# SmallBatSAO.net
KiCad netlist of a schematic drawn in EAGLE
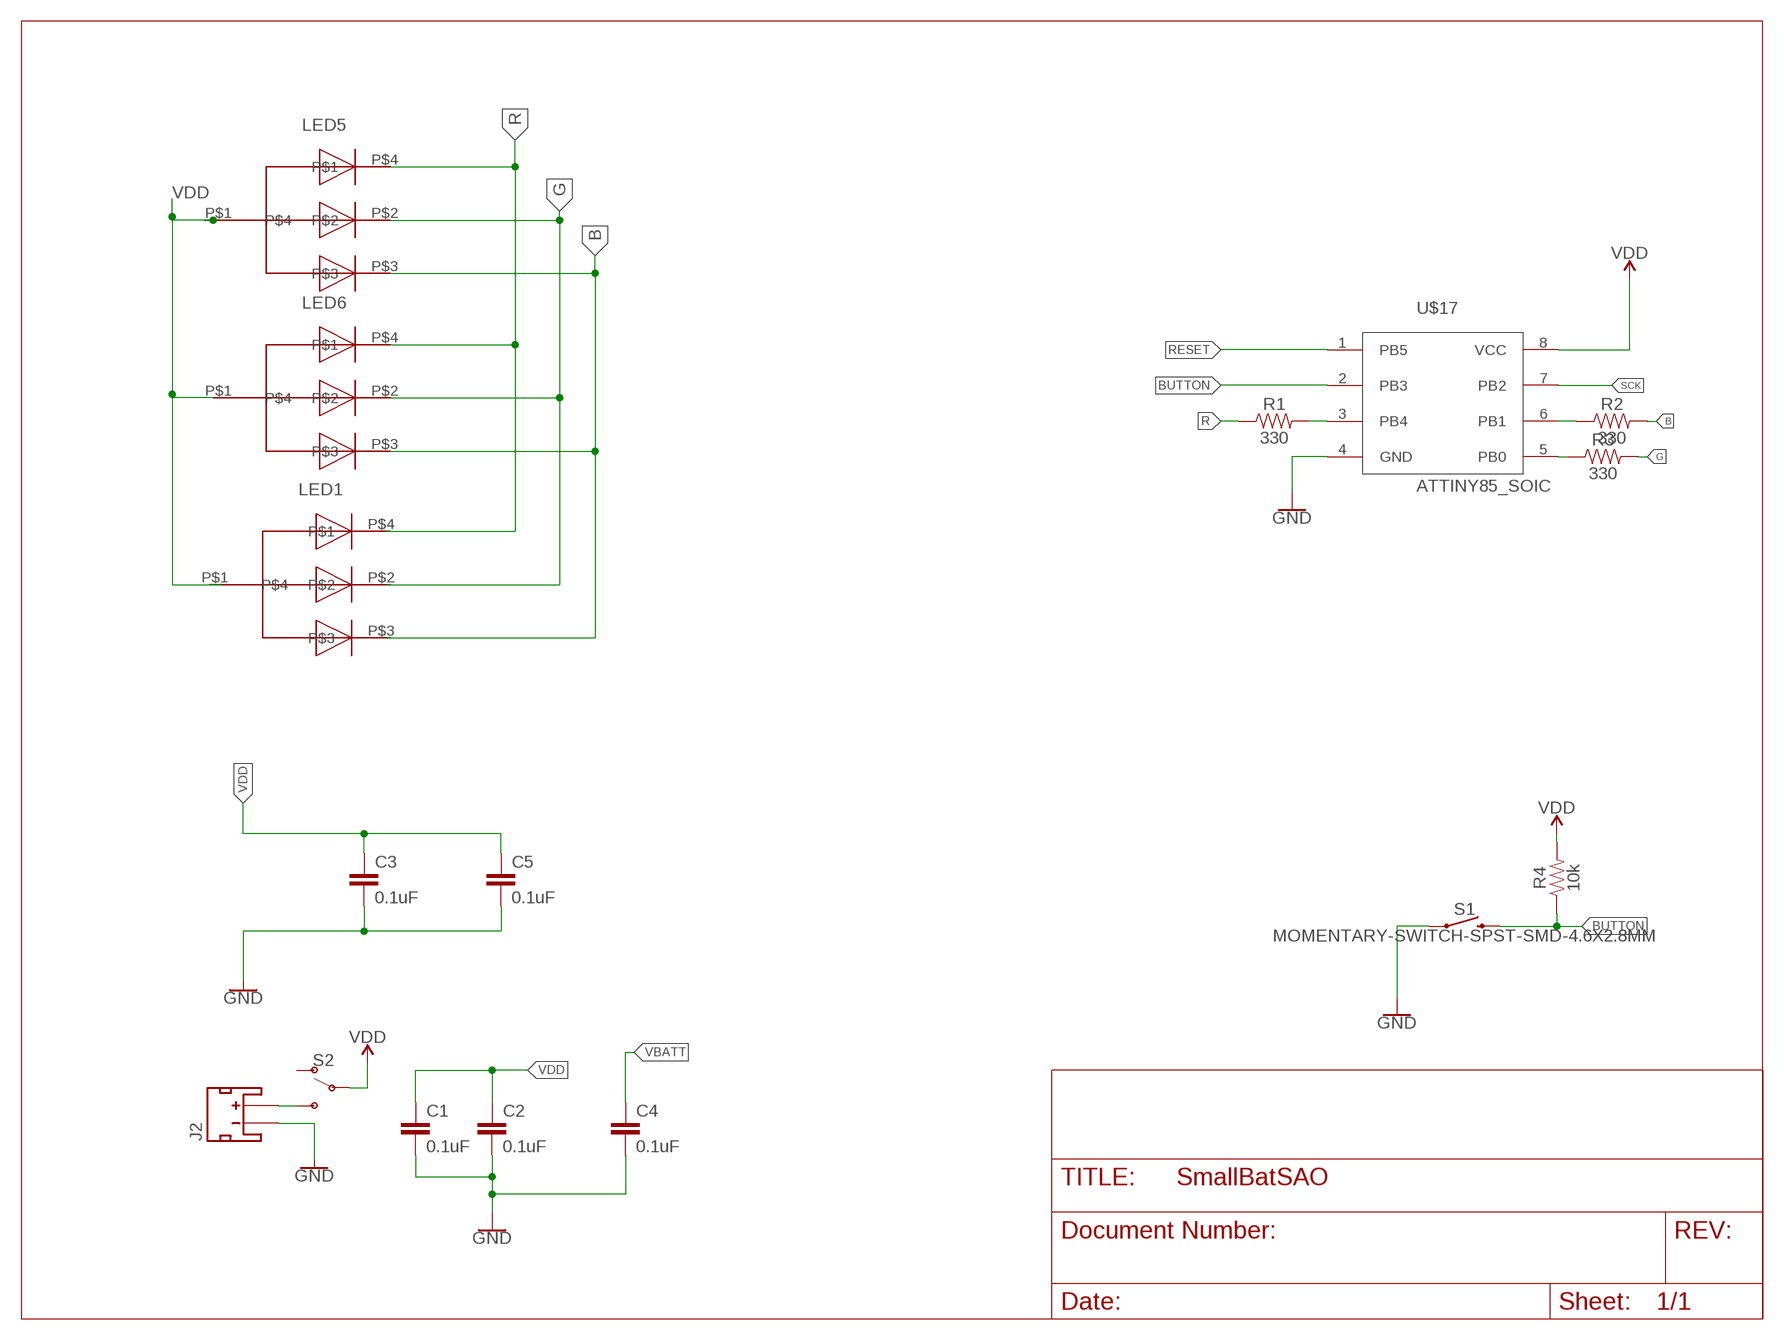
[diagram p0: schematic, sheet 1]

(export (version "E")
  (design (tool "Eeschema 10.0.6"))
  (components
    (comp (ref "C1")
      (value "0.1uF")
      (footprint "eagle-import:0603")
      (libsource (lib "eagle-import") (part "0.1UF-0603-25V-(+80/-20%)"))
    )
    (comp (ref "C2")
      (value "0.1uF")
      (footprint "eagle-import:0603")
      (libsource (lib "eagle-import") (part "0.1UF-0603-25V-(+80/-20%)"))
    )
    (comp (ref "C3")
      (value "0.1uF")
      (footprint "eagle-import:0603")
      (libsource (lib "eagle-import") (part "0.1UF-0603-25V-(+80/-20%)"))
    )
    (comp (ref "C4")
      (value "0.1uF")
      (footprint "eagle-import:0603")
      (libsource (lib "eagle-import") (part "0.1UF-0603-25V-(+80/-20%)"))
    )
    (comp (ref "C5")
      (value "0.1uF")
      (footprint "eagle-import:0603")
      (libsource (lib "eagle-import") (part "0.1UF-0603-25V-(+80/-20%)"))
    )
    (comp (ref "J2")
      (value "JST_2MM_MALE")
      (footprint "eagle-import:JST-2-SMD")
      (libsource (lib "eagle-import") (part "JST_2MM_MALE"))
    )
    (comp (ref "LED1")
      (value "PLCC4_REVERSE_MOUNT")
      (footprint "eagle-import:PLCC4_SMD_REVERSE_MOUNT_LED")
      (fields (field (name "DIGIKEYPARTNO") "1497-1257-1-ND ") (field (name "PARTNO") "XZMDKCBDDG45S-9"))
      (libsource (lib "eagle-import") (part "PLCC4_REVERSE_MOUNT"))
    )
    (comp (ref "LED5")
      (value "PLCC4_REVERSE_MOUNT")
      (footprint "eagle-import:PLCC4_SMD_REVERSE_MOUNT_LED")
      (fields (field (name "DIGIKEYPARTNO") "1497-1257-1-ND ") (field (name "PARTNO") "XZMDKCBDDG45S-9"))
      (libsource (lib "eagle-import") (part "PLCC4_REVERSE_MOUNT"))
    )
    (comp (ref "LED6")
      (value "PLCC4_REVERSE_MOUNT")
      (footprint "eagle-import:PLCC4_SMD_REVERSE_MOUNT_LED")
      (fields (field (name "DIGIKEYPARTNO") "1497-1257-1-ND ") (field (name "PARTNO") "XZMDKCBDDG45S-9"))
      (libsource (lib "eagle-import") (part "PLCC4_REVERSE_MOUNT"))
    )
    (comp (ref "R1")
      (value "330")
      (footprint "eagle-import:0603")
      (libsource (lib "eagle-import") (part "330OHM-0603-1/10W-1%"))
    )
    (comp (ref "R2")
      (value "330")
      (footprint "eagle-import:0603")
      (libsource (lib "eagle-import") (part "330OHM-0603-1/10W-1%"))
    )
    (comp (ref "R3")
      (value "330")
      (footprint "eagle-import:0603")
      (libsource (lib "eagle-import") (part "330OHM-0603-1/10W-1%"))
    )
    (comp (ref "R4")
      (value "10k")
      (footprint "eagle-import:0603")
      (libsource (lib "eagle-import") (part "10KOHM-0603-1/10W-1%"))
    )
    (comp (ref "S1")
      (value "MOMENTARY-SWITCH-SPST-SMD-4.6X2.8MM")
      (footprint "eagle-import:TACTILE_SWITCH_SMD_4.6X2.8MM")
      (libsource (lib "eagle-import") (part "MOMENTARY-SWITCH-SPST-SMD-4.6X2.8MM"))
    )
    (comp (ref "S2")
      (value "SWITCH-SPDT-SMD-AYZ0202")
      (footprint "eagle-import:SWITCH_DPDT_SMD_AYZ0202")
      (libsource (lib "eagle-import") (part "SWITCH-SPDT-SMD-AYZ0202"))
    )
    (comp (ref "U$17")
      (value "ATTINY85_SOIC")
      (footprint "eagle-import:SOIC-8")
      (libsource (lib "eagle-import") (part "ATTINY85_SOIC"))
    )
  )
  (nets
    (net (code "1") (name "B") (class "Default")
      (node (ref "LED1") (pin "P$3") (pinfunction "P$3_P$3") (pintype "bidirectional"))
      (node (ref "LED5") (pin "P$3") (pinfunction "P$3_P$3") (pintype "bidirectional"))
      (node (ref "LED6") (pin "P$3") (pinfunction "P$3_P$3") (pintype "bidirectional"))
      (node (ref "R2") (pin "2") (pinfunction "2_2") (pintype "passive"))
    )
    (net (code "2") (name "BUTTON") (class "Default")
      (node (ref "R4") (pin "1") (pinfunction "1_1") (pintype "passive"))
      (node (ref "S1") (pin "3") (pinfunction "2_3") (pintype "passive"))
      (node (ref "S1") (pin "4") (pinfunction "2_4") (pintype "passive"))
      (node (ref "U$17") (pin "2") (pinfunction "PB3_2") (pintype "bidirectional"))
    )
    (net (code "3") (name "G") (class "Default")
      (node (ref "LED1") (pin "P$2") (pinfunction "P$2_P$2") (pintype "bidirectional"))
      (node (ref "LED5") (pin "P$2") (pinfunction "P$2_P$2") (pintype "bidirectional"))
      (node (ref "LED6") (pin "P$2") (pinfunction "P$2_P$2") (pintype "bidirectional"))
      (node (ref "R3") (pin "2") (pinfunction "2_2") (pintype "passive"))
    )
    (net (code "4") (name "GND") (class "Default")
      (node (ref "C1") (pin "2") (pinfunction "2_2") (pintype "passive"))
      (node (ref "C2") (pin "2") (pinfunction "2_2") (pintype "passive"))
      (node (ref "C3") (pin "2") (pinfunction "2_2") (pintype "passive"))
      (node (ref "C4") (pin "2") (pinfunction "2_2") (pintype "passive"))
      (node (ref "C5") (pin "2") (pinfunction "2_2") (pintype "passive"))
      (node (ref "J2") (pin "1") (pinfunction "-_1") (pintype "bidirectional"))
      (node (ref "S1") (pin "1") (pinfunction "1_1") (pintype "passive"))
      (node (ref "S1") (pin "2") (pinfunction "1_2") (pintype "passive"))
      (node (ref "U$17") (pin "4") (pinfunction "GND_4") (pintype "bidirectional"))
    )
    (net (code "5") (name "Net-(U$17-PB0)") (class "Default")
      (node (ref "R3") (pin "1") (pinfunction "1_1") (pintype "passive"))
      (node (ref "U$17") (pin "5") (pinfunction "PB0_5") (pintype "bidirectional"))
    )
    (net (code "6") (name "Net-(U$17-PB1)") (class "Default")
      (node (ref "R2") (pin "1") (pinfunction "1_1") (pintype "passive"))
      (node (ref "U$17") (pin "6") (pinfunction "PB1_6") (pintype "bidirectional"))
    )
    (net (code "7") (name "Net-(U$17-PB4)") (class "Default")
      (node (ref "R1") (pin "2") (pinfunction "2_2") (pintype "passive"))
      (node (ref "U$17") (pin "3") (pinfunction "PB4_3") (pintype "bidirectional"))
    )
    (net (code "8") (name "R") (class "Default")
      (node (ref "LED1") (pin "P$4") (pinfunction "P$1_P$4") (pintype "bidirectional"))
      (node (ref "LED5") (pin "P$4") (pinfunction "P$1_P$4") (pintype "bidirectional"))
      (node (ref "LED6") (pin "P$4") (pinfunction "P$1_P$4") (pintype "bidirectional"))
      (node (ref "R1") (pin "1") (pinfunction "1_1") (pintype "passive"))
    )
    (net (code "9") (name "RESET") (class "Default")
      (node (ref "U$17") (pin "1") (pinfunction "PB5_1") (pintype "bidirectional"))
    )
    (net (code "10") (name "SCK") (class "Default")
      (node (ref "U$17") (pin "7") (pinfunction "PB2_7") (pintype "bidirectional"))
    )
    (net (code "11") (name "VBATT") (class "Default")
      (node (ref "C4") (pin "1") (pinfunction "1_1") (pintype "passive"))
      (node (ref "J2") (pin "2") (pinfunction "+_2") (pintype "bidirectional"))
      (node (ref "S2") (pin "3") (pinfunction "S_3") (pintype "passive"))
    )
    (net (code "12") (name "VDD") (class "Default")
      (node (ref "C1") (pin "1") (pinfunction "1_1") (pintype "passive"))
      (node (ref "C2") (pin "1") (pinfunction "1_1") (pintype "passive"))
      (node (ref "C3") (pin "1") (pinfunction "1_1") (pintype "passive"))
      (node (ref "C5") (pin "1") (pinfunction "1_1") (pintype "passive"))
      (node (ref "LED1") (pin "P$1") (pinfunction "P$4_P$1") (pintype "bidirectional"))
      (node (ref "LED5") (pin "P$1") (pinfunction "P$4_P$1") (pintype "bidirectional"))
      (node (ref "LED6") (pin "P$1") (pinfunction "P$4_P$1") (pintype "bidirectional"))
      (node (ref "R4") (pin "2") (pinfunction "2_2") (pintype "passive"))
      (node (ref "S2") (pin "2") (pinfunction "P_2") (pintype "passive"))
      (node (ref "U$17") (pin "8") (pinfunction "VCC_8") (pintype "bidirectional"))
    )
    (net (code "13") (name "unconnected-(J2-PAD1-PadNC1)") (class "Default")
      (node (ref "J2") (pin "NC1") (pinfunction "PAD1_NC1") (pintype "bidirectional"))
    )
    (net (code "14") (name "unconnected-(J2-PAD2-PadNC2)") (class "Default")
      (node (ref "J2") (pin "NC2") (pinfunction "PAD2_NC2") (pintype "bidirectional"))
    )
    (net (code "15") (name "unconnected-(S2-O-Pad1)") (class "Default")
      (node (ref "S2") (pin "1") (pinfunction "O_1") (pintype "passive"))
    )
  )
)
